# VentingSysPCB.net
KiCad netlist of a schematic drawn in EAGLE
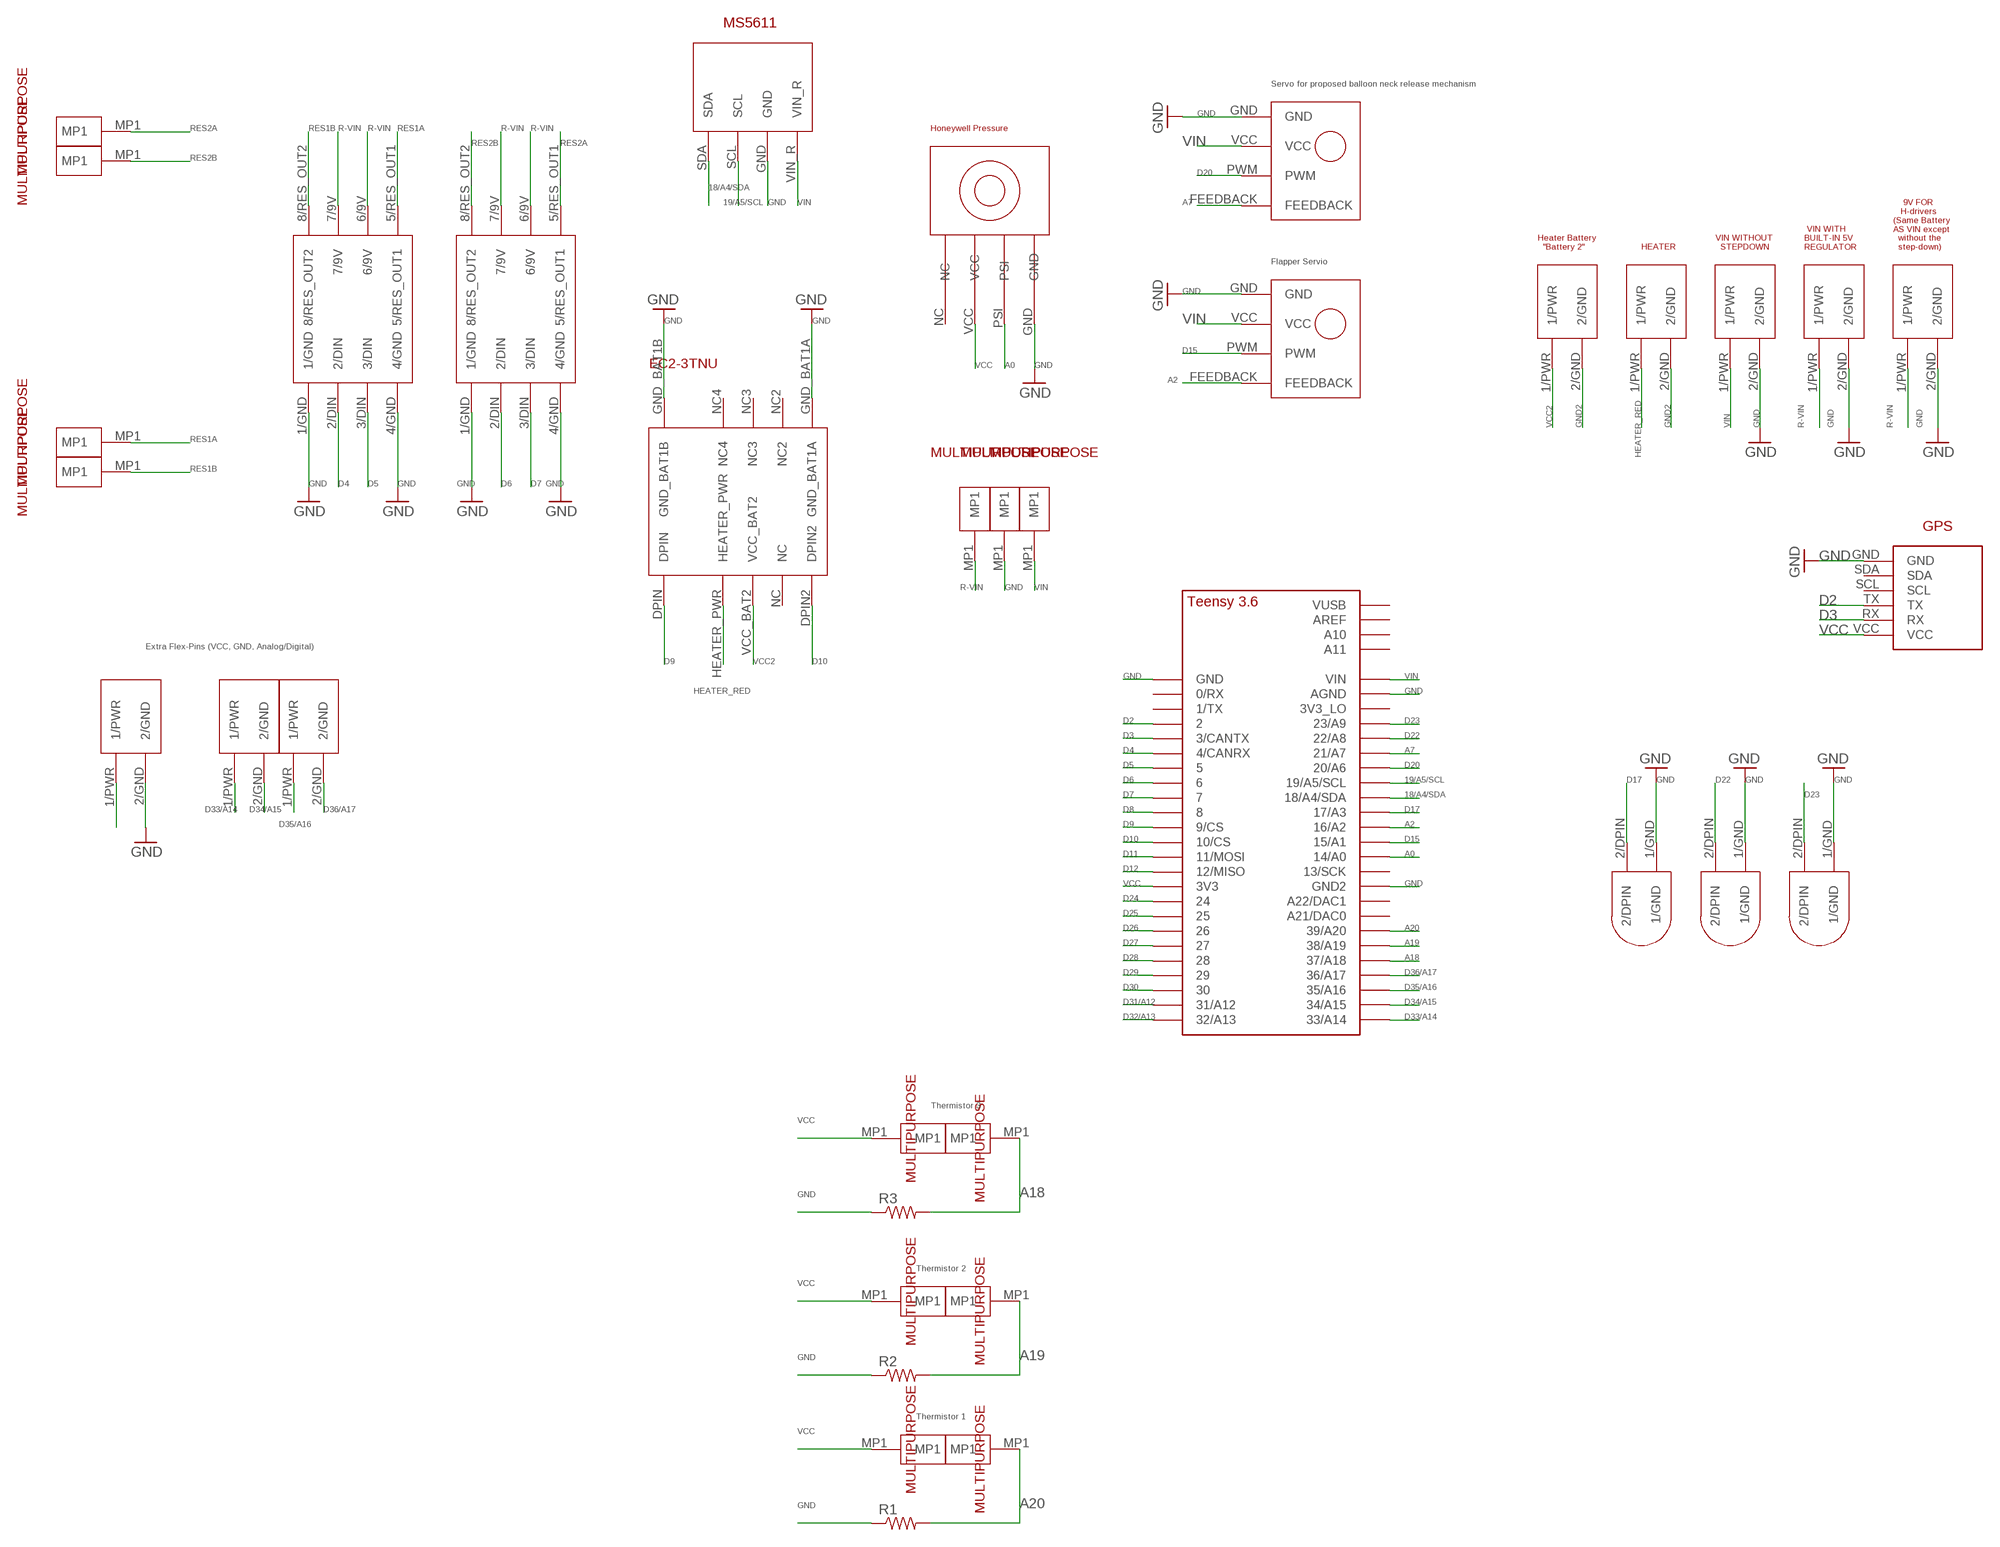
[diagram p0: schematic, sheet 1]

(export (version "E")
  (design (tool "Eeschema 10.0.6"))
  (components
    (comp (ref "R1")
      (value "R-US_0204/7")
      (footprint "eagle-import:0204_7")
      (libsource (lib "eagle-import") (part "R-US_0204/7"))
    )
    (comp (ref "R2")
      (value "R-US_0204/7")
      (footprint "eagle-import:0204_7")
      (libsource (lib "eagle-import") (part "R-US_0204/7"))
    )
    (comp (ref "R3")
      (value "R-US_0204/7")
      (footprint "eagle-import:0204_7")
      (libsource (lib "eagle-import") (part "R-US_0204/7"))
    )
    (comp (ref "U$1")
      (value "MULTIPURPOSE")
      (footprint "eagle-import:MULTIPURPOSE")
      (libsource (lib "eagle-import") (part "MULTIPURPOSE"))
    )
    (comp (ref "U$2")
      (value "TEENSY_3.5/3.6_BASIC")
      (footprint "eagle-import:TEENSY_3.5_3.6_BASIC")
      (libsource (lib "eagle-import") (part "TEENSY_3.5/3.6_BASIC"))
    )
    (comp (ref "U$3")
      (value "MULTIPURPOSE")
      (footprint "eagle-import:MULTIPURPOSE")
      (libsource (lib "eagle-import") (part "MULTIPURPOSE"))
    )
    (comp (ref "U$4")
      (value "3V3_H-DRIVER")
      (footprint "eagle-import:3V3_H-DRIVER")
      (libsource (lib "eagle-import") (part "3V3_H-DRIVER"))
    )
    (comp (ref "U$5")
      (value "MULTIPURPOSE")
      (footprint "eagle-import:MULTIPURPOSE")
      (libsource (lib "eagle-import") (part "MULTIPURPOSE"))
    )
    (comp (ref "U$6")
      (value "3V3_H-DRIVER")
      (footprint "eagle-import:3V3_H-DRIVER")
      (libsource (lib "eagle-import") (part "3V3_H-DRIVER"))
    )
    (comp (ref "U$7")
      (value "ADAFRUIT_LED")
      (footprint "eagle-import:ADAFRUIT_LED")
      (libsource (lib "eagle-import") (part "ADAFRUIT_LED"))
    )
    (comp (ref "U$8")
      (value "MULTIPURPOSE")
      (footprint "eagle-import:MULTIPURPOSE")
      (libsource (lib "eagle-import") (part "MULTIPURPOSE"))
    )
    (comp (ref "U$10")
      (value "MULTIPURPOSE")
      (footprint "eagle-import:MULTIPURPOSE")
      (libsource (lib "eagle-import") (part "MULTIPURPOSE"))
    )
    (comp (ref "U$12")
      (value "ADAFRUIT_LED")
      (footprint "eagle-import:ADAFRUIT_LED")
      (libsource (lib "eagle-import") (part "ADAFRUIT_LED"))
    )
    (comp (ref "U$13")
      (value "ADAFRUIT_LED")
      (footprint "eagle-import:ADAFRUIT_LED")
      (libsource (lib "eagle-import") (part "ADAFRUIT_LED"))
    )
    (comp (ref "U$14")
      (value "MULTIPURPOSE")
      (footprint "eagle-import:MULTIPURPOSE")
      (libsource (lib "eagle-import") (part "MULTIPURPOSE"))
    )
    (comp (ref "U$15")
      (value "MULTIPURPOSE")
      (footprint "eagle-import:MULTIPURPOSE")
      (libsource (lib "eagle-import") (part "MULTIPURPOSE"))
    )
    (comp (ref "U$16")
      (value "EC2-3TNU_LATCH_RELAY")
      (footprint "eagle-import:EC2-3TNU_LATCH_RELAY")
      (libsource (lib "eagle-import") (part "EC2-3TNU_LATCH_RELAY"))
    )
    (comp (ref "U$17")
      (value "FEEDBACK_SERVO")
      (footprint "eagle-import:FEEDBACK_SERVO")
      (libsource (lib "eagle-import") (part "FEEDBACK_SERVO"))
    )
    (comp (ref "U$18")
      (value "HONEYWELL_PRESSURE")
      (footprint "eagle-import:HONEYWELL_PRESSURE")
      (libsource (lib "eagle-import") (part "HONEYWELL_PRESSURE"))
    )
    (comp (ref "U$19")
      (value "MS5611_PRESSURE")
      (footprint "eagle-import:MS5611_PRESSURE")
      (libsource (lib "eagle-import") (part "MS5611_PRESSURE"))
    )
    (comp (ref "U$20")
      (value "MULTIPURPOSE")
      (footprint "eagle-import:MULTIPURPOSE")
      (libsource (lib "eagle-import") (part "MULTIPURPOSE"))
    )
    (comp (ref "U$21")
      (value "MULTIPURPOSE")
      (footprint "eagle-import:MULTIPURPOSE")
      (libsource (lib "eagle-import") (part "MULTIPURPOSE"))
    )
    (comp (ref "U$22")
      (value "MULTIPURPOSE")
      (footprint "eagle-import:MULTIPURPOSE")
      (libsource (lib "eagle-import") (part "MULTIPURPOSE"))
    )
    (comp (ref "U$23")
      (value "MULTIPURPOSE")
      (footprint "eagle-import:MULTIPURPOSE")
      (libsource (lib "eagle-import") (part "MULTIPURPOSE"))
    )
    (comp (ref "U$24")
      (value "TERMINAL_BLOCK")
      (footprint "eagle-import:TERMINAL_BLOCK")
      (libsource (lib "eagle-import") (part "TERMINAL_BLOCK"))
    )
    (comp (ref "U$25")
      (value "TERMINAL_BLOCK")
      (footprint "eagle-import:TERMINAL_BLOCK")
      (libsource (lib "eagle-import") (part "TERMINAL_BLOCK"))
    )
    (comp (ref "U$26")
      (value "TERMINAL_BLOCK")
      (footprint "eagle-import:TERMINAL_BLOCK")
      (libsource (lib "eagle-import") (part "TERMINAL_BLOCK"))
    )
    (comp (ref "U$27")
      (value "TERMINAL_BLOCK")
      (footprint "eagle-import:TERMINAL_BLOCK")
      (libsource (lib "eagle-import") (part "TERMINAL_BLOCK"))
    )
    (comp (ref "U$28")
      (value "TERMINAL_BLOCK")
      (footprint "eagle-import:TERMINAL_BLOCK")
      (libsource (lib "eagle-import") (part "TERMINAL_BLOCK"))
    )
    (comp (ref "U$29")
      (value "UBLOX-8-GPS")
      (footprint "eagle-import:UBLOX-8-NEO")
      (libsource (lib "eagle-import") (part "UBLOX-8-GPS"))
    )
    (comp (ref "U$30")
      (value "FEEDBACK_SERVO")
      (footprint "eagle-import:FEEDBACK_SERVO")
      (libsource (lib "eagle-import") (part "FEEDBACK_SERVO"))
    )
    (comp (ref "U$31")
      (value "TERMINAL_BLOCK")
      (footprint "eagle-import:TERMINAL_BLOCK")
      (libsource (lib "eagle-import") (part "TERMINAL_BLOCK"))
    )
    (comp (ref "U$32")
      (value "TERMINAL_BLOCK")
      (footprint "eagle-import:TERMINAL_BLOCK")
      (libsource (lib "eagle-import") (part "TERMINAL_BLOCK"))
    )
    (comp (ref "U$33")
      (value "TERMINAL_BLOCK")
      (footprint "eagle-import:TERMINAL_BLOCK")
      (libsource (lib "eagle-import") (part "TERMINAL_BLOCK"))
    )
    (comp (ref "U$34")
      (value "MULTIPURPOSE")
      (footprint "eagle-import:MULTIPURPOSE")
      (libsource (lib "eagle-import") (part "MULTIPURPOSE"))
    )
    (comp (ref "U$35")
      (value "MULTIPURPOSE")
      (footprint "eagle-import:MULTIPURPOSE")
      (libsource (lib "eagle-import") (part "MULTIPURPOSE"))
    )
  )
  (nets
    (net (code "1") (name "/18{slash}A4{slash}SDA") (class "Default")
      (node (ref "U$19") (pin "SDA") (pinfunction "SDA_SDA") (pintype "bidirectional"))
      (node (ref "U$2") (pin "18/A4/SDA") (pinfunction "18/A4/SDA_18/A4/SDA") (pintype "bidirectional"))
    )
    (net (code "2") (name "/19{slash}A5{slash}SCL") (class "Default")
      (node (ref "U$19") (pin "SCL") (pinfunction "SCL_SCL") (pintype "bidirectional"))
      (node (ref "U$2") (pin "19/A5/SCL") (pinfunction "19/A5/SCL_19/A5/SCL") (pintype "bidirectional"))
    )
    (net (code "3") (name "/A0") (class "Default")
      (node (ref "U$18") (pin "PSI") (pinfunction "PSI_PSI") (pintype "bidirectional"))
      (node (ref "U$2") (pin "14/A0") (pinfunction "14/A0_14/A0") (pintype "bidirectional"))
    )
    (net (code "4") (name "/A2") (class "Default")
      (node (ref "U$17") (pin "FEEDBACK") (pinfunction "FEEDBACK_FEEDBACK") (pintype "bidirectional"))
      (node (ref "U$2") (pin "16/A2") (pinfunction "16/A2_16/A2") (pintype "bidirectional"))
    )
    (net (code "5") (name "/A7") (class "Default")
      (node (ref "U$2") (pin "21/A7") (pinfunction "21/A7_21/A7") (pintype "bidirectional"))
      (node (ref "U$30") (pin "FEEDBACK") (pinfunction "FEEDBACK_FEEDBACK") (pintype "bidirectional"))
    )
    (net (code "6") (name "/A18") (class "Default")
      (node (ref "R3") (pin "2") (pinfunction "2_2") (pintype "passive"))
      (node (ref "U$2") (pin "37/A18") (pinfunction "37/A18_37/A18") (pintype "bidirectional"))
      (node (ref "U$5") (pin "MP1") (pinfunction "MP1_MP1") (pintype "bidirectional"))
    )
    (net (code "7") (name "/A19") (class "Default")
      (node (ref "R2") (pin "2") (pinfunction "2_2") (pintype "passive"))
      (node (ref "U$14") (pin "MP1") (pinfunction "MP1_MP1") (pintype "bidirectional"))
      (node (ref "U$2") (pin "38/A19") (pinfunction "38/A19_38/A19") (pintype "bidirectional"))
    )
    (net (code "8") (name "/A20") (class "Default")
      (node (ref "R1") (pin "2") (pinfunction "2_2") (pintype "passive"))
      (node (ref "U$2") (pin "39/A20") (pinfunction "39/A20_39/A20") (pintype "bidirectional"))
      (node (ref "U$34") (pin "MP1") (pinfunction "MP1_MP1") (pintype "bidirectional"))
    )
    (net (code "9") (name "/D2") (class "Default")
      (node (ref "U$2") (pin "2") (pinfunction "2_2") (pintype "bidirectional"))
      (node (ref "U$29") (pin "TX") (pinfunction "TX_TX") (pintype "bidirectional"))
    )
    (net (code "10") (name "/D3") (class "Default")
      (node (ref "U$2") (pin "3/CANTX") (pinfunction "3/CANTX_3/CANTX") (pintype "bidirectional"))
      (node (ref "U$29") (pin "RX") (pinfunction "RX_RX") (pintype "bidirectional"))
    )
    (net (code "11") (name "/D4") (class "Default")
      (node (ref "U$2") (pin "4/CANRX") (pinfunction "4/CANRX_4/CANRX") (pintype "bidirectional"))
      (node (ref "U$6") (pin "2/DIN") (pinfunction "2/DIN_2/DIN") (pintype "bidirectional"))
    )
    (net (code "12") (name "/D5") (class "Default")
      (node (ref "U$2") (pin "5") (pinfunction "5_5") (pintype "bidirectional"))
      (node (ref "U$6") (pin "3/DIN") (pinfunction "3/DIN_3/DIN") (pintype "bidirectional"))
    )
    (net (code "13") (name "/D6") (class "Default")
      (node (ref "U$2") (pin "6") (pinfunction "6_6") (pintype "bidirectional"))
      (node (ref "U$4") (pin "2/DIN") (pinfunction "2/DIN_2/DIN") (pintype "bidirectional"))
    )
    (net (code "14") (name "/D7") (class "Default")
      (node (ref "U$2") (pin "7") (pinfunction "7_7") (pintype "bidirectional"))
      (node (ref "U$4") (pin "3/DIN") (pinfunction "3/DIN_3/DIN") (pintype "bidirectional"))
    )
    (net (code "15") (name "/D8") (class "Default")
      (node (ref "U$2") (pin "8") (pinfunction "8_8") (pintype "bidirectional"))
    )
    (net (code "16") (name "/D9") (class "Default")
      (node (ref "U$16") (pin "DPIN") (pinfunction "DPIN_DPIN") (pintype "bidirectional"))
      (node (ref "U$2") (pin "9/CS") (pinfunction "9/CS_9/CS") (pintype "bidirectional"))
    )
    (net (code "17") (name "/D10") (class "Default")
      (node (ref "U$16") (pin "DPIN2") (pinfunction "DPIN2_DPIN2") (pintype "bidirectional"))
      (node (ref "U$2") (pin "10/CS") (pinfunction "10/CS_10/CS") (pintype "bidirectional"))
    )
    (net (code "18") (name "/D11") (class "Default")
      (node (ref "U$2") (pin "11/MOSI") (pinfunction "11/MOSI_11/MOSI") (pintype "bidirectional"))
    )
    (net (code "19") (name "/D12") (class "Default")
      (node (ref "U$2") (pin "12/MISO") (pinfunction "12/MISO_12/MISO") (pintype "bidirectional"))
    )
    (net (code "20") (name "/D15") (class "Default")
      (node (ref "U$17") (pin "PWM") (pinfunction "PWM_PWM") (pintype "bidirectional"))
      (node (ref "U$2") (pin "15/A1") (pinfunction "15/A1_15/A1") (pintype "bidirectional"))
    )
    (net (code "21") (name "/D17") (class "Default")
      (node (ref "U$2") (pin "17/A3") (pinfunction "17/A3_17/A3") (pintype "bidirectional"))
      (node (ref "U$7") (pin "2/DPIN") (pinfunction "2/DPIN_2/DPIN") (pintype "bidirectional"))
    )
    (net (code "22") (name "/D20") (class "Default")
      (node (ref "U$2") (pin "20/A6") (pinfunction "20/A6_20/A6") (pintype "bidirectional"))
      (node (ref "U$30") (pin "PWM") (pinfunction "PWM_PWM") (pintype "bidirectional"))
    )
    (net (code "23") (name "/D22") (class "Default")
      (node (ref "U$12") (pin "2/DPIN") (pinfunction "2/DPIN_2/DPIN") (pintype "bidirectional"))
      (node (ref "U$2") (pin "22/A8") (pinfunction "22/A8_22/A8") (pintype "bidirectional"))
    )
    (net (code "24") (name "/D23") (class "Default")
      (node (ref "U$13") (pin "2/DPIN") (pinfunction "2/DPIN_2/DPIN") (pintype "bidirectional"))
      (node (ref "U$2") (pin "23/A9") (pinfunction "23/A9_23/A9") (pintype "bidirectional"))
    )
    (net (code "25") (name "/D24") (class "Default")
      (node (ref "U$2") (pin "24") (pinfunction "24_24") (pintype "bidirectional"))
    )
    (net (code "26") (name "/D25") (class "Default")
      (node (ref "U$2") (pin "25") (pinfunction "25_25") (pintype "bidirectional"))
    )
    (net (code "27") (name "/D26") (class "Default")
      (node (ref "U$2") (pin "26") (pinfunction "26_26") (pintype "bidirectional"))
    )
    (net (code "28") (name "/D27") (class "Default")
      (node (ref "U$2") (pin "27") (pinfunction "27_27") (pintype "bidirectional"))
    )
    (net (code "29") (name "/D28") (class "Default")
      (node (ref "U$2") (pin "28") (pinfunction "28_28") (pintype "bidirectional"))
    )
    (net (code "30") (name "/D29") (class "Default")
      (node (ref "U$2") (pin "29") (pinfunction "29_29") (pintype "bidirectional"))
    )
    (net (code "31") (name "/D30") (class "Default")
      (node (ref "U$2") (pin "30") (pinfunction "30_30") (pintype "bidirectional"))
    )
    (net (code "32") (name "/D31{slash}A12") (class "Default")
      (node (ref "U$2") (pin "31/A12") (pinfunction "31/A12_31/A12") (pintype "bidirectional"))
    )
    (net (code "33") (name "/D32{slash}A13") (class "Default")
      (node (ref "U$2") (pin "32/A13") (pinfunction "32/A13_32/A13") (pintype "bidirectional"))
    )
    (net (code "34") (name "/D33{slash}A14") (class "Default")
      (node (ref "U$2") (pin "33/A14") (pinfunction "33/A14_33/A14") (pintype "bidirectional"))
      (node (ref "U$32") (pin "1/PWR") (pinfunction "1/PWR_1/PWR") (pintype "bidirectional"))
    )
    (net (code "35") (name "/D34{slash}A15") (class "Default")
      (node (ref "U$2") (pin "34/A15") (pinfunction "34/A15_34/A15") (pintype "bidirectional"))
      (node (ref "U$32") (pin "2/GND") (pinfunction "2/GND_2/GND") (pintype "bidirectional"))
    )
    (net (code "36") (name "/D35{slash}A16") (class "Default")
      (node (ref "U$2") (pin "35/A16") (pinfunction "35/A16_35/A16") (pintype "bidirectional"))
      (node (ref "U$33") (pin "1/PWR") (pinfunction "1/PWR_1/PWR") (pintype "bidirectional"))
    )
    (net (code "37") (name "/D36{slash}A17") (class "Default")
      (node (ref "U$2") (pin "36/A17") (pinfunction "36/A17_36/A17") (pintype "bidirectional"))
      (node (ref "U$33") (pin "2/GND") (pinfunction "2/GND_2/GND") (pintype "bidirectional"))
    )
    (net (code "38") (name "/GND2") (class "Default")
      (node (ref "U$24") (pin "2/GND") (pinfunction "2/GND_2/GND") (pintype "bidirectional"))
      (node (ref "U$25") (pin "2/GND") (pinfunction "2/GND_2/GND") (pintype "bidirectional"))
    )
    (net (code "39") (name "/HEATER_RED") (class "Default")
      (node (ref "U$16") (pin "HEATER_PWR") (pinfunction "HEATER_PWR_HEATER_PWR") (pintype "bidirectional"))
      (node (ref "U$25") (pin "1/PWR") (pinfunction "1/PWR_1/PWR") (pintype "bidirectional"))
    )
    (net (code "40") (name "/R-VIN") (class "Default")
      (node (ref "U$1") (pin "MP1") (pinfunction "MP1_MP1") (pintype "bidirectional"))
      (node (ref "U$27") (pin "1/PWR") (pinfunction "1/PWR_1/PWR") (pintype "bidirectional"))
      (node (ref "U$28") (pin "1/PWR") (pinfunction "1/PWR_1/PWR") (pintype "bidirectional"))
      (node (ref "U$4") (pin "6/9V") (pinfunction "6/9V_6/9V") (pintype "bidirectional"))
      (node (ref "U$4") (pin "7/9V") (pinfunction "7/9V_7/9V") (pintype "bidirectional"))
      (node (ref "U$6") (pin "6/9V") (pinfunction "6/9V_6/9V") (pintype "bidirectional"))
      (node (ref "U$6") (pin "7/9V") (pinfunction "7/9V_7/9V") (pintype "bidirectional"))
    )
    (net (code "41") (name "/RES1A") (class "Default")
      (node (ref "U$21") (pin "MP1") (pinfunction "MP1_MP1") (pintype "bidirectional"))
      (node (ref "U$6") (pin "5/RES_OUT1") (pinfunction "5/RES_OUT1_5/RES_OUT1") (pintype "bidirectional"))
    )
    (net (code "42") (name "/RES1B") (class "Default")
      (node (ref "U$20") (pin "MP1") (pinfunction "MP1_MP1") (pintype "bidirectional"))
      (node (ref "U$6") (pin "8/RES_OUT2") (pinfunction "8/RES_OUT2_8/RES_OUT2") (pintype "bidirectional"))
    )
    (net (code "43") (name "/RES2A") (class "Default")
      (node (ref "U$23") (pin "MP1") (pinfunction "MP1_MP1") (pintype "bidirectional"))
      (node (ref "U$4") (pin "5/RES_OUT1") (pinfunction "5/RES_OUT1_5/RES_OUT1") (pintype "bidirectional"))
    )
    (net (code "44") (name "/RES2B") (class "Default")
      (node (ref "U$22") (pin "MP1") (pinfunction "MP1_MP1") (pintype "bidirectional"))
      (node (ref "U$4") (pin "8/RES_OUT2") (pinfunction "8/RES_OUT2_8/RES_OUT2") (pintype "bidirectional"))
    )
    (net (code "45") (name "/VCC") (class "Default")
      (node (ref "U$10") (pin "MP1") (pinfunction "MP1_MP1") (pintype "bidirectional"))
      (node (ref "U$15") (pin "MP1") (pinfunction "MP1_MP1") (pintype "bidirectional"))
      (node (ref "U$18") (pin "VCC") (pinfunction "VCC_VCC") (pintype "bidirectional"))
      (node (ref "U$2") (pin "3V3") (pinfunction "3V3_3V3") (pintype "bidirectional"))
      (node (ref "U$29") (pin "VCC") (pinfunction "VCC_VCC") (pintype "bidirectional"))
      (node (ref "U$31") (pin "1/PWR") (pinfunction "1/PWR_1/PWR") (pintype "bidirectional"))
      (node (ref "U$35") (pin "MP1") (pinfunction "MP1_MP1") (pintype "bidirectional"))
    )
    (net (code "46") (name "/VCC2") (class "Default")
      (node (ref "U$16") (pin "VCC_BAT2") (pinfunction "VCC_BAT2_VCC_BAT2") (pintype "bidirectional"))
      (node (ref "U$24") (pin "1/PWR") (pinfunction "1/PWR_1/PWR") (pintype "bidirectional"))
    )
    (net (code "47") (name "/VIN") (class "Default")
      (node (ref "U$17") (pin "VCC") (pinfunction "VCC_VCC") (pintype "bidirectional"))
      (node (ref "U$19") (pin "VIN_R") (pinfunction "VIN_R_VIN_R") (pintype "bidirectional"))
      (node (ref "U$2") (pin "VIN") (pinfunction "VIN_VIN") (pintype "bidirectional"))
      (node (ref "U$26") (pin "1/PWR") (pinfunction "1/PWR_1/PWR") (pintype "bidirectional"))
      (node (ref "U$30") (pin "VCC") (pinfunction "VCC_VCC") (pintype "bidirectional"))
      (node (ref "U$8") (pin "MP1") (pinfunction "MP1_MP1") (pintype "bidirectional"))
    )
    (net (code "48") (name "GND") (class "Default")
      (node (ref "R1") (pin "1") (pinfunction "1_1") (pintype "passive"))
      (node (ref "R2") (pin "1") (pinfunction "1_1") (pintype "passive"))
      (node (ref "R3") (pin "1") (pinfunction "1_1") (pintype "passive"))
      (node (ref "U$12") (pin "1/GND") (pinfunction "1/GND_1/GND") (pintype "bidirectional"))
      (node (ref "U$13") (pin "1/GND") (pinfunction "1/GND_1/GND") (pintype "bidirectional"))
      (node (ref "U$16") (pin "GND_BAT1A") (pinfunction "GND_BAT1A_GND_BAT1A") (pintype "bidirectional"))
      (node (ref "U$16") (pin "GND_BAT1B") (pinfunction "GND_BAT1B_GND_BAT1B") (pintype "bidirectional"))
      (node (ref "U$17") (pin "GND") (pinfunction "GND_GND") (pintype "bidirectional"))
      (node (ref "U$18") (pin "GND") (pinfunction "GND_GND") (pintype "bidirectional"))
      (node (ref "U$19") (pin "GND") (pinfunction "GND_GND") (pintype "bidirectional"))
      (node (ref "U$2") (pin "AGND") (pinfunction "AGND_AGND") (pintype "bidirectional"))
      (node (ref "U$2") (pin "GND") (pinfunction "GND_GND") (pintype "bidirectional"))
      (node (ref "U$2") (pin "GND2") (pinfunction "GND2_GND2") (pintype "bidirectional"))
      (node (ref "U$26") (pin "2/GND") (pinfunction "2/GND_2/GND") (pintype "bidirectional"))
      (node (ref "U$27") (pin "2/GND") (pinfunction "2/GND_2/GND") (pintype "bidirectional"))
      (node (ref "U$28") (pin "2/GND") (pinfunction "2/GND_2/GND") (pintype "bidirectional"))
      (node (ref "U$29") (pin "GND") (pinfunction "GND_GND") (pintype "bidirectional"))
      (node (ref "U$3") (pin "MP1") (pinfunction "MP1_MP1") (pintype "bidirectional"))
      (node (ref "U$30") (pin "GND") (pinfunction "GND_GND") (pintype "bidirectional"))
      (node (ref "U$31") (pin "2/GND") (pinfunction "2/GND_2/GND") (pintype "bidirectional"))
      (node (ref "U$4") (pin "1/GND") (pinfunction "1/GND_1/GND") (pintype "bidirectional"))
      (node (ref "U$4") (pin "4/GND") (pinfunction "4/GND_4/GND") (pintype "bidirectional"))
      (node (ref "U$6") (pin "1/GND") (pinfunction "1/GND_1/GND") (pintype "bidirectional"))
      (node (ref "U$6") (pin "4/GND") (pinfunction "4/GND_4/GND") (pintype "bidirectional"))
      (node (ref "U$7") (pin "1/GND") (pinfunction "1/GND_1/GND") (pintype "bidirectional"))
    )
    (net (code "49") (name "unconnected-(U$2-A21{slash}DAC0-Pad21{slash}DAC0)") (class "Default")
      (node (ref "U$2") (pin "21/DAC0") (pinfunction "A21/DAC0_21/DAC0") (pintype "bidirectional"))
    )
    (net (code "50") (name "unconnected-(U$2-Pad0{slash}RX)") (class "Default")
      (node (ref "U$2") (pin "0/RX") (pinfunction "0/RX_0/RX") (pintype "bidirectional"))
    )
    (net (code "51") (name "unconnected-(U$2-Pad1{slash}TX)") (class "Default")
      (node (ref "U$2") (pin "1/TX") (pinfunction "1/TX_1/TX") (pintype "bidirectional"))
    )
    (net (code "52") (name "unconnected-(U$2-Pad3V3_LO)") (class "Default")
      (node (ref "U$2") (pin "3V3_LO") (pinfunction "3V3_LO_3V3_LO") (pintype "bidirectional"))
    )
    (net (code "53") (name "unconnected-(U$2-Pad13{slash}SCK)") (class "Default")
      (node (ref "U$2") (pin "13/SCK") (pinfunction "13/SCK_13/SCK") (pintype "bidirectional"))
    )
    (net (code "54") (name "unconnected-(U$2-PadA10)") (class "Default")
      (node (ref "U$2") (pin "A10") (pinfunction "A10_A10") (pintype "bidirectional"))
    )
    (net (code "55") (name "unconnected-(U$2-PadA11)") (class "Default")
      (node (ref "U$2") (pin "A11") (pinfunction "A11_A11") (pintype "bidirectional"))
    )
    (net (code "56") (name "unconnected-(U$2-PadA22{slash}DAC1)") (class "Default")
      (node (ref "U$2") (pin "A22/DAC1") (pinfunction "A22/DAC1_A22/DAC1") (pintype "bidirectional"))
    )
    (net (code "57") (name "unconnected-(U$2-PadAREF)") (class "Default")
      (node (ref "U$2") (pin "AREF") (pinfunction "AREF_AREF") (pintype "bidirectional"))
    )
    (net (code "58") (name "unconnected-(U$2-PadVUSB)") (class "Default")
      (node (ref "U$2") (pin "VUSB") (pinfunction "VUSB_VUSB") (pintype "bidirectional"))
    )
    (net (code "59") (name "unconnected-(U$16-PadNC)") (class "Default")
      (node (ref "U$16") (pin "NC") (pinfunction "NC_NC") (pintype "bidirectional"))
    )
    (net (code "60") (name "unconnected-(U$16-PadNC2)") (class "Default")
      (node (ref "U$16") (pin "NC2") (pinfunction "NC2_NC2") (pintype "bidirectional"))
    )
    (net (code "61") (name "unconnected-(U$16-PadNC3)") (class "Default")
      (node (ref "U$16") (pin "NC3") (pinfunction "NC3_NC3") (pintype "bidirectional"))
    )
    (net (code "62") (name "unconnected-(U$16-PadNC4)") (class "Default")
      (node (ref "U$16") (pin "NC4") (pinfunction "NC4_NC4") (pintype "bidirectional"))
    )
    (net (code "63") (name "unconnected-(U$18-PadNC)") (class "Default")
      (node (ref "U$18") (pin "NC") (pinfunction "NC_NC") (pintype "bidirectional"))
    )
    (net (code "64") (name "unconnected-(U$29-PadSCL)") (class "Default")
      (node (ref "U$29") (pin "SCL") (pinfunction "SCL_SCL") (pintype "bidirectional"))
    )
    (net (code "65") (name "unconnected-(U$29-PadSDA)") (class "Default")
      (node (ref "U$29") (pin "SDA") (pinfunction "SDA_SDA") (pintype "bidirectional"))
    )
  )
)
